# HASP_Electronics.net
KiCad netlist of a schematic drawn in EAGLE
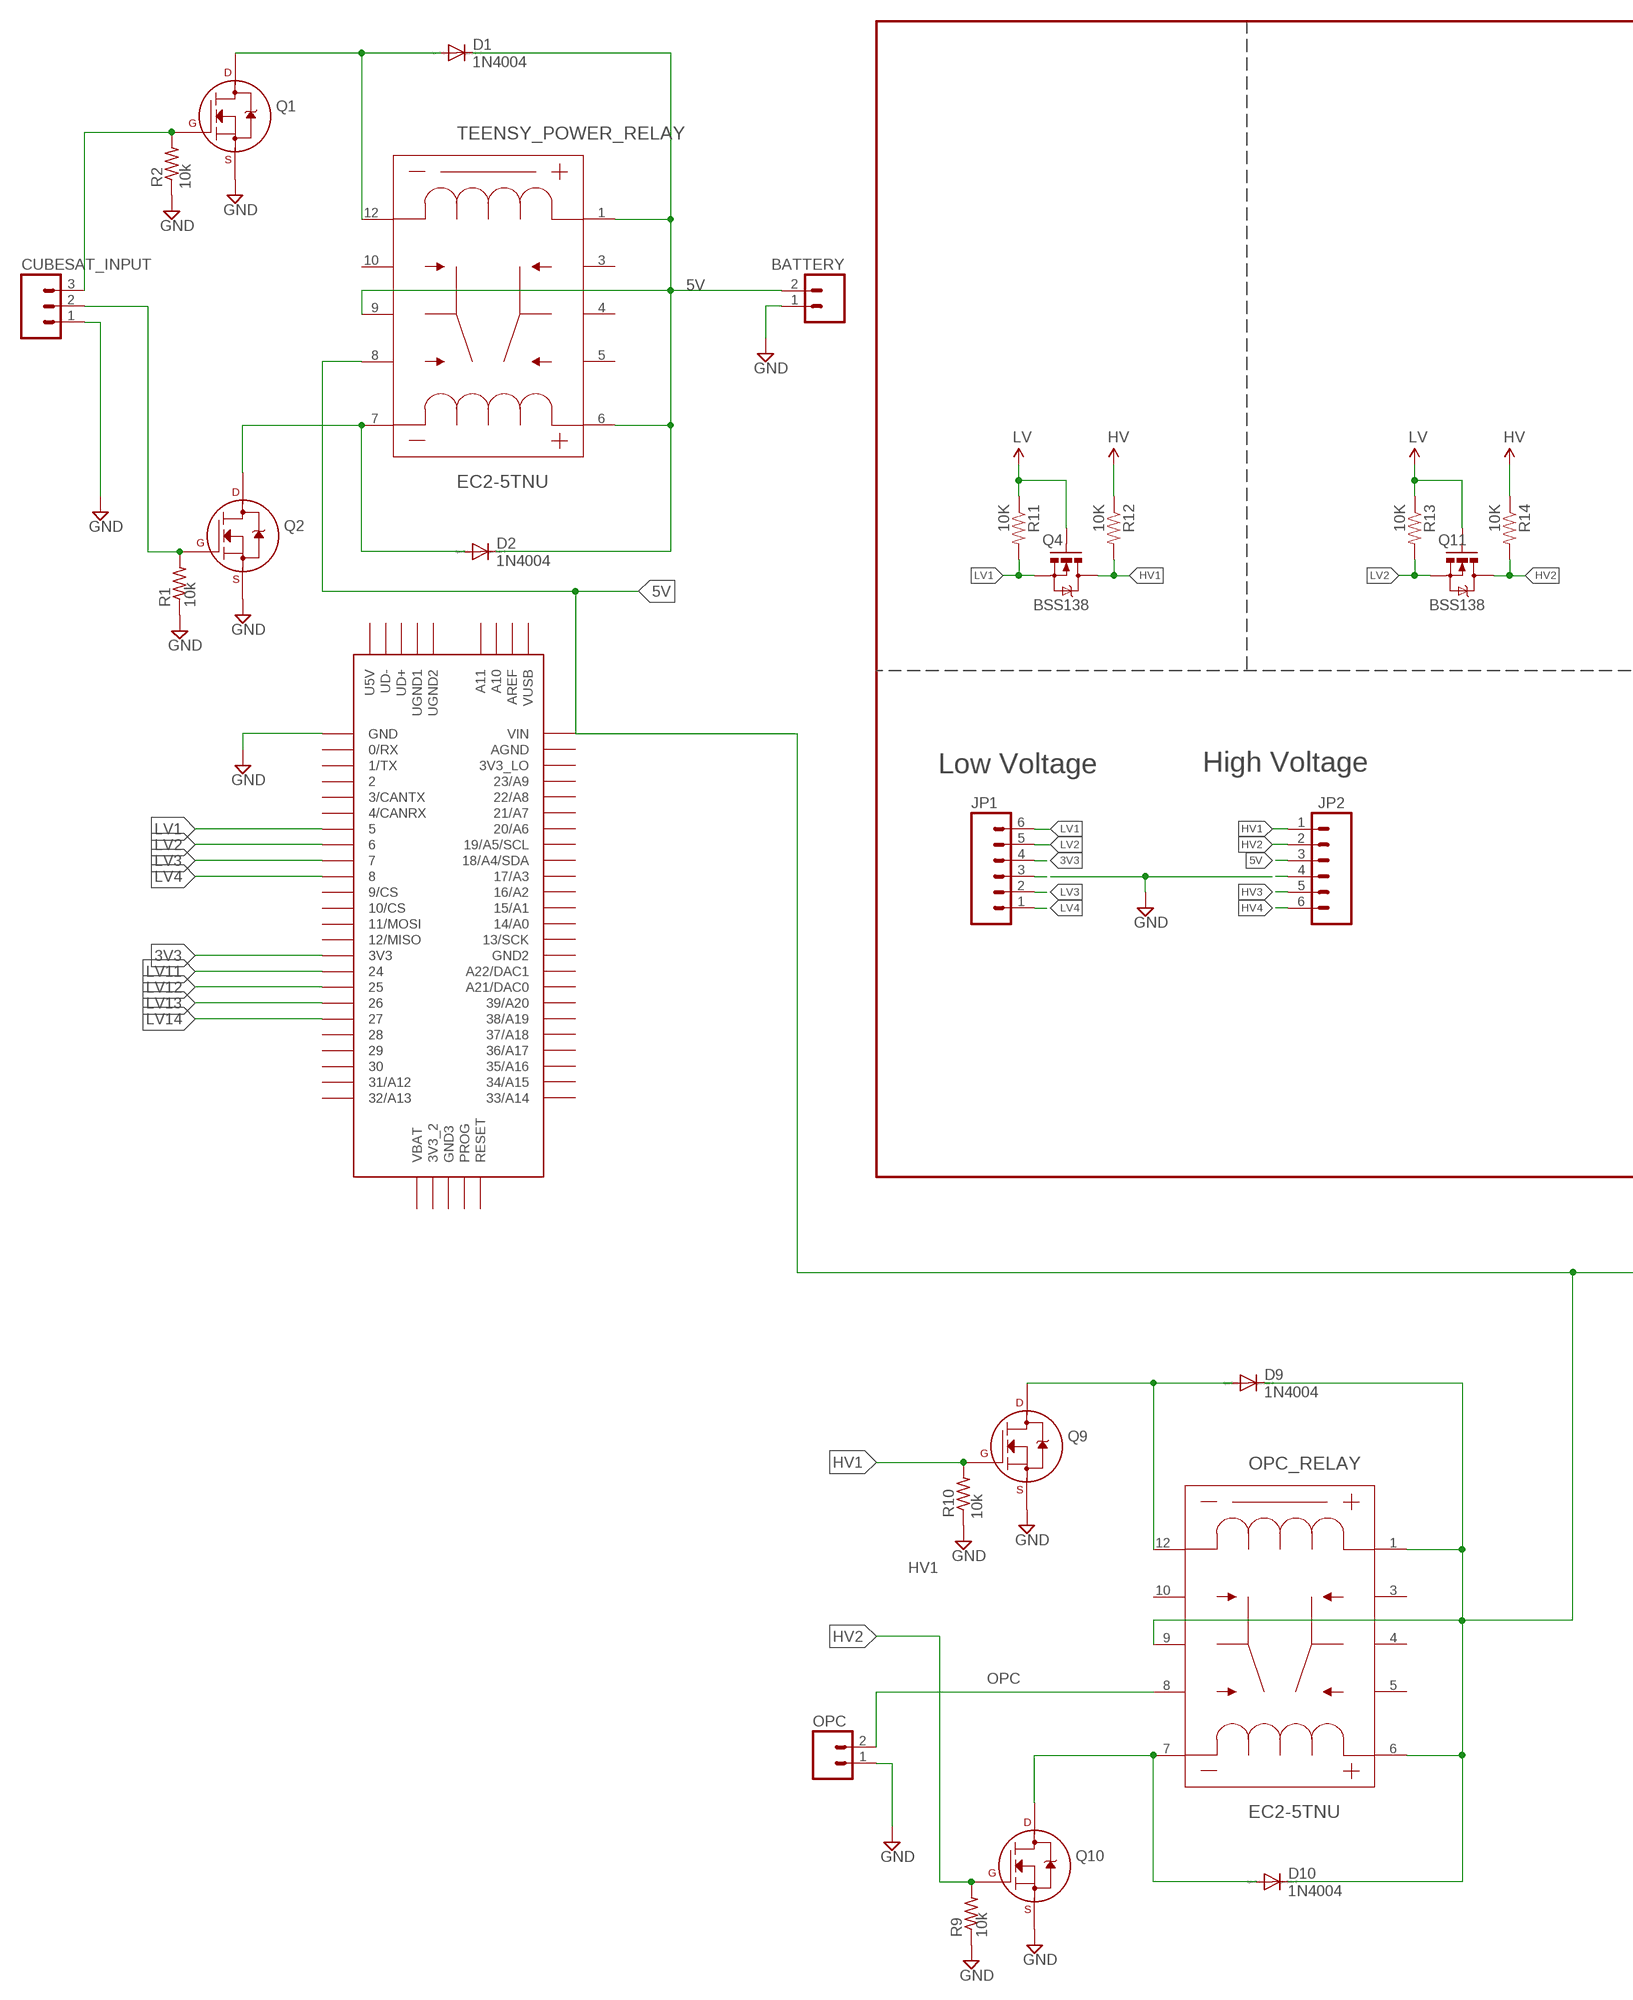
[diagram p0: schematic, sheet 1, part 1 of 2]
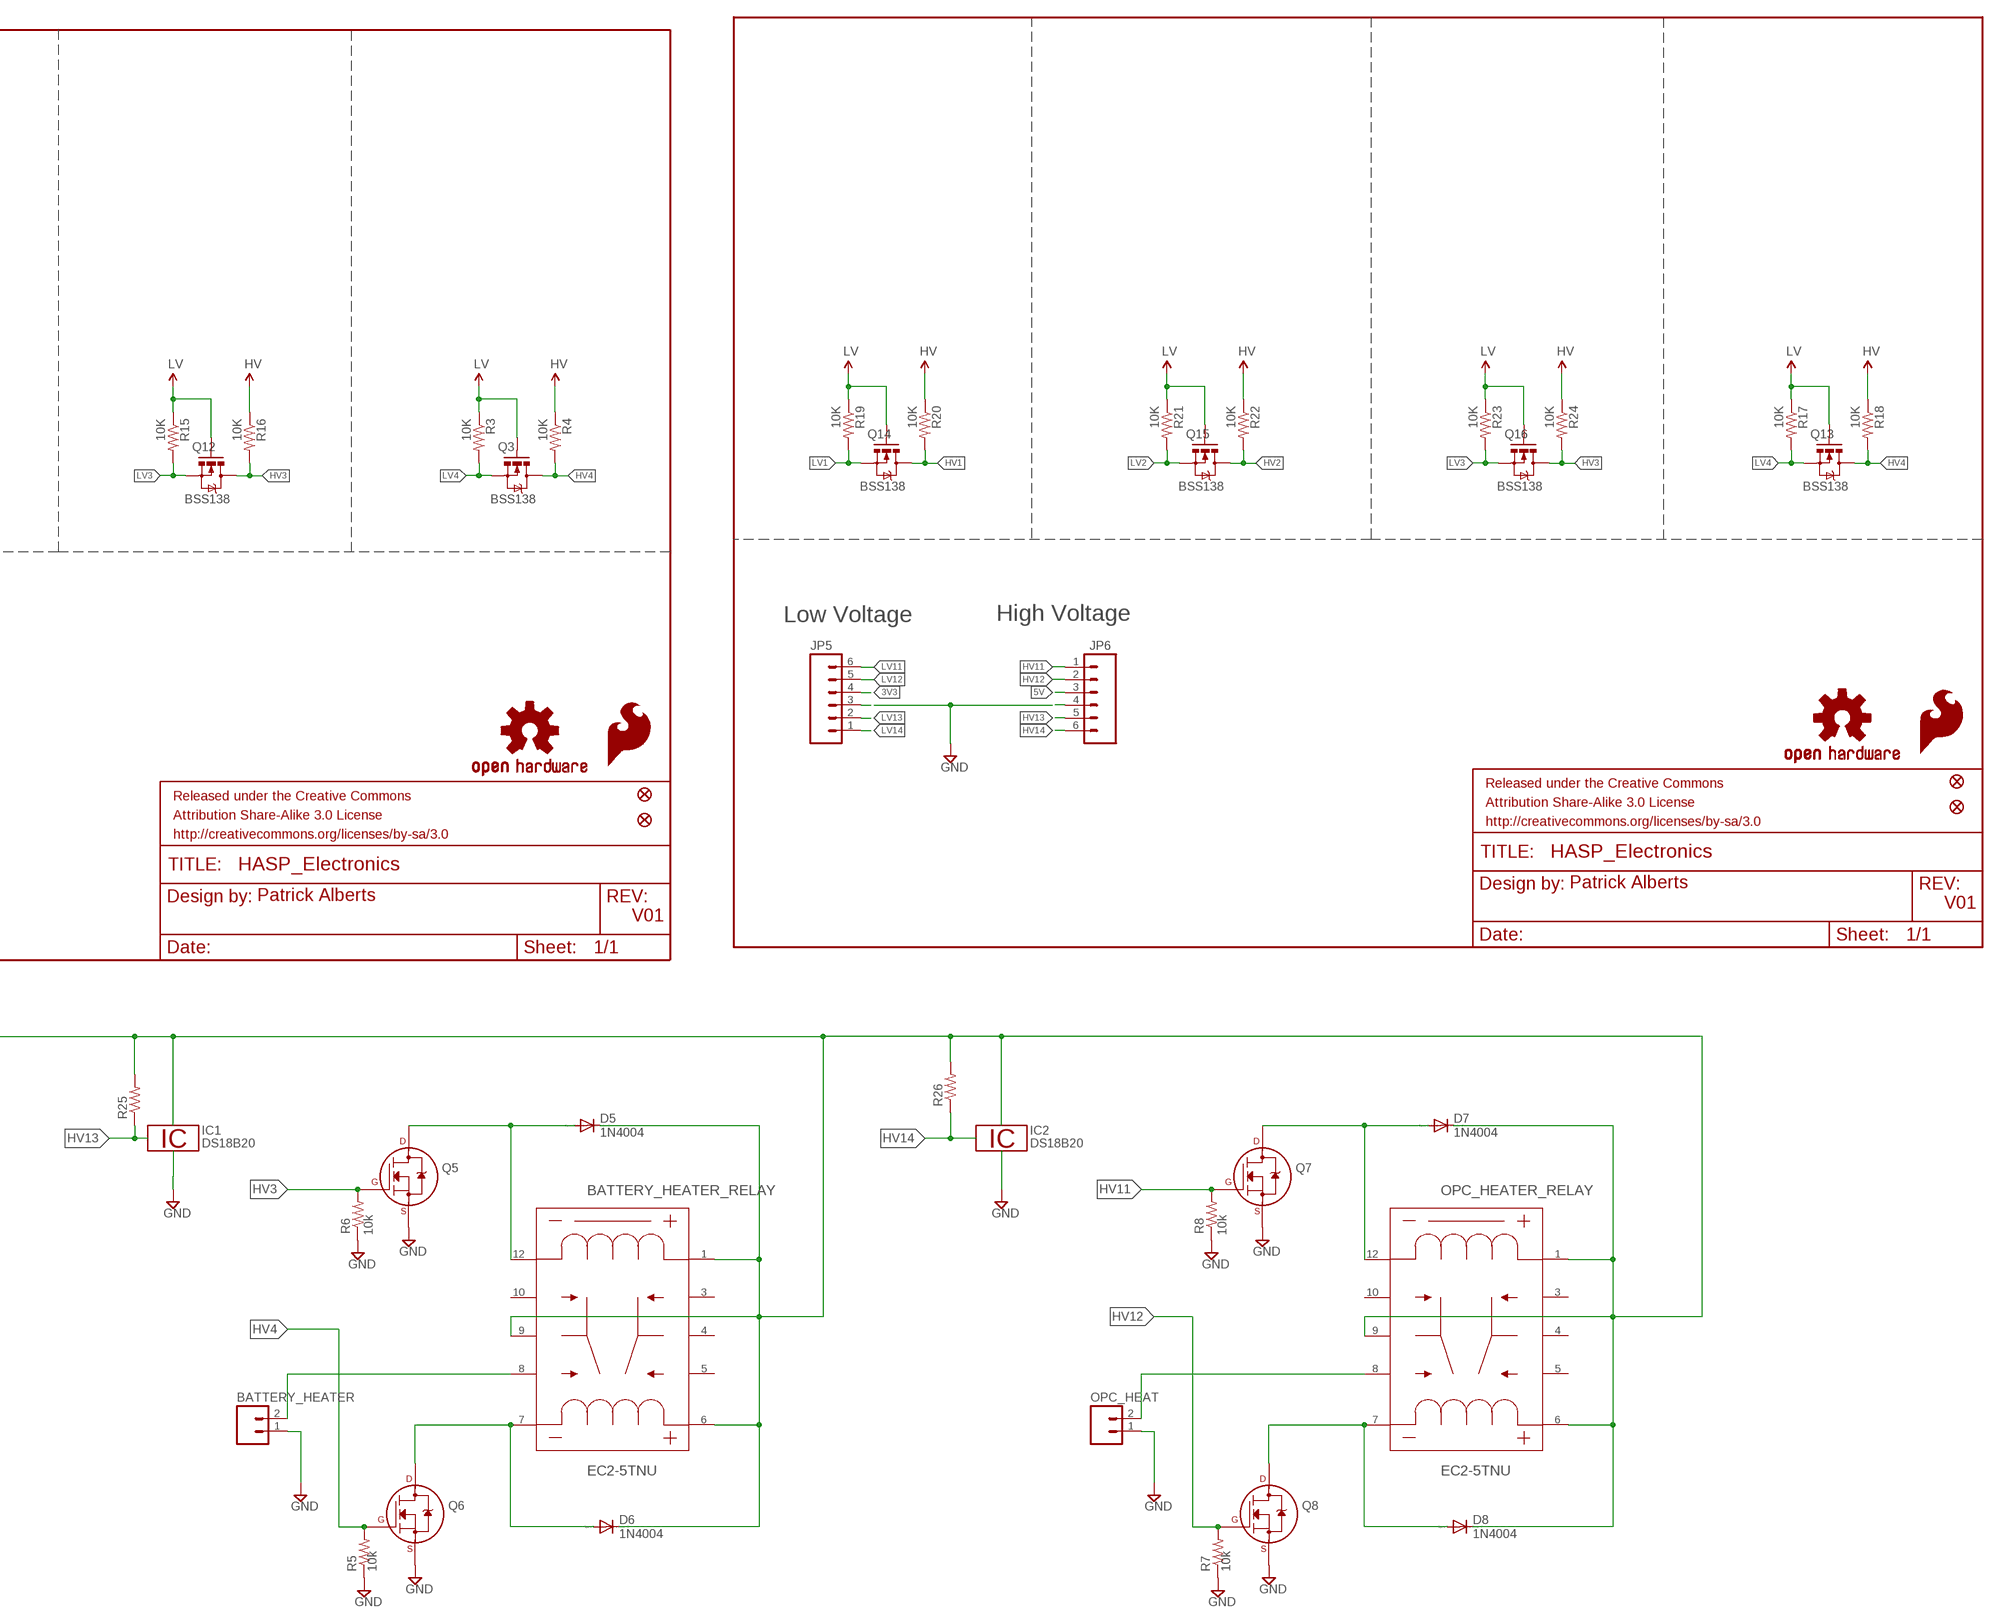
[diagram p1: schematic, sheet 1, part 2 of 2]

(export (version "E")
  (design (tool "Eeschema 10.0.6"))
  (components
    (comp (ref "BATTERY")
      (value "M02")
      (footprint "eagle-import:02P")
      (libsource (lib "eagle-import") (part "M02"))
    )
    (comp (ref "BATTERY_HEATER")
      (value "M02")
      (footprint "eagle-import:02P")
      (libsource (lib "eagle-import") (part "M02"))
    )
    (comp (ref "BATTERY_HEATER_RELAY")
      (value "EC2-5TNU")
      (footprint "eagle-import:EC2TNU")
      (fields (field (name "MANUFACTURER_PART_NUMBER") "EC25TNU"))
      (libsource (lib "eagle-import") (part "EC2-5TNU"))
    )
    (comp (ref "CUBESAT_INPUT")
      (value "M03")
      (footprint "eagle-import:03P")
      (libsource (lib "eagle-import") (part "M03"))
    )
    (comp (ref "D1")
      (value "1N4004")
      (footprint "eagle-import:DO41-10")
      (libsource (lib "eagle-import") (part "1N4004"))
    )
    (comp (ref "D2")
      (value "1N4004")
      (footprint "eagle-import:DO41-10")
      (libsource (lib "eagle-import") (part "1N4004"))
    )
    (comp (ref "D5")
      (value "1N4004")
      (footprint "eagle-import:DO41-10")
      (libsource (lib "eagle-import") (part "1N4004"))
    )
    (comp (ref "D6")
      (value "1N4004")
      (footprint "eagle-import:DO41-10")
      (libsource (lib "eagle-import") (part "1N4004"))
    )
    (comp (ref "D7")
      (value "1N4004")
      (footprint "eagle-import:DO41-10")
      (libsource (lib "eagle-import") (part "1N4004"))
    )
    (comp (ref "D8")
      (value "1N4004")
      (footprint "eagle-import:DO41-10")
      (libsource (lib "eagle-import") (part "1N4004"))
    )
    (comp (ref "D9")
      (value "1N4004")
      (footprint "eagle-import:DO41-10")
      (libsource (lib "eagle-import") (part "1N4004"))
    )
    (comp (ref "D10")
      (value "1N4004")
      (footprint "eagle-import:DO41-10")
      (libsource (lib "eagle-import") (part "1N4004"))
    )
    (comp (ref "IC1")
      (value "DS18B20")
      (footprint "eagle-import:TO92-")
      (libsource (lib "eagle-import") (part "DS18B20"))
    )
    (comp (ref "IC2")
      (value "DS18B20")
      (footprint "eagle-import:TO92-")
      (libsource (lib "eagle-import") (part "DS18B20"))
    )
    (comp (ref "JP1")
      (value "M06SIP")
      (footprint "eagle-import:1X06")
      (libsource (lib "eagle-import") (part "M06SIP"))
    )
    (comp (ref "JP2")
      (value "M06SIP")
      (footprint "eagle-import:1X06")
      (libsource (lib "eagle-import") (part "M06SIP"))
    )
    (comp (ref "JP3")
      (value "FIDUCIALUFIDUCIAL")
      (footprint "eagle-import:MICRO-FIDUCIAL")
      (libsource (lib "eagle-import") (part "FIDUCIALUFIDUCIAL"))
    )
    (comp (ref "JP4")
      (value "FIDUCIALUFIDUCIAL")
      (footprint "eagle-import:MICRO-FIDUCIAL")
      (libsource (lib "eagle-import") (part "FIDUCIALUFIDUCIAL"))
    )
    (comp (ref "JP5")
      (value "M06SIP")
      (footprint "eagle-import:1X06")
      (libsource (lib "eagle-import") (part "M06SIP"))
    )
    (comp (ref "JP6")
      (value "M06SIP")
      (footprint "eagle-import:1X06")
      (libsource (lib "eagle-import") (part "M06SIP"))
    )
    (comp (ref "JP7")
      (value "FIDUCIALUFIDUCIAL")
      (footprint "eagle-import:MICRO-FIDUCIAL")
      (libsource (lib "eagle-import") (part "FIDUCIALUFIDUCIAL"))
    )
    (comp (ref "JP8")
      (value "FIDUCIALUFIDUCIAL")
      (footprint "eagle-import:MICRO-FIDUCIAL")
      (libsource (lib "eagle-import") (part "FIDUCIALUFIDUCIAL"))
    )
    (comp (ref "LOGO1")
      (value "SFE_LOGO_FLAME.1_INCH")
      (footprint "eagle-import:SFE_LOGO_FLAME_.1")
      (libsource (lib "eagle-import") (part "SFE_LOGO_FLAME.1_INCH"))
    )
    (comp (ref "LOGO2")
      (value "OSHW-LOGOS")
      (footprint "eagle-import:OSHW-LOGO-S")
      (libsource (lib "eagle-import") (part "OSHW-LOGOS"))
    )
    (comp (ref "LOGO3")
      (value "SFE_LOGO_FLAME.1_INCH")
      (footprint "eagle-import:SFE_LOGO_FLAME_.1")
      (libsource (lib "eagle-import") (part "SFE_LOGO_FLAME.1_INCH"))
    )
    (comp (ref "LOGO4")
      (value "OSHW-LOGOS")
      (footprint "eagle-import:OSHW-LOGO-S")
      (libsource (lib "eagle-import") (part "OSHW-LOGOS"))
    )
    (comp (ref "OPC")
      (value "M02")
      (footprint "eagle-import:02P")
      (libsource (lib "eagle-import") (part "M02"))
    )
    (comp (ref "OPC_HEAT")
      (value "M02")
      (footprint "eagle-import:02P")
      (libsource (lib "eagle-import") (part "M02"))
    )
    (comp (ref "OPC_HEATER_RELAY")
      (value "EC2-5TNU")
      (footprint "eagle-import:EC2TNU")
      (fields (field (name "MANUFACTURER_PART_NUMBER") "EC25TNU"))
      (libsource (lib "eagle-import") (part "EC2-5TNU"))
    )
    (comp (ref "OPC_RELAY")
      (value "EC2-5TNU")
      (footprint "eagle-import:EC2TNU")
      (fields (field (name "MANUFACTURER_PART_NUMBER") "EC25TNU"))
      (libsource (lib "eagle-import") (part "EC2-5TNU"))
    )
    (comp (ref "Q1")
      (value "2N7000_TO92")
      (footprint "eagle-import:TO-92")
      (libsource (lib "eagle-import") (part "2N700_TO920"))
    )
    (comp (ref "Q2")
      (value "2N7000_TO92")
      (footprint "eagle-import:TO-92")
      (libsource (lib "eagle-import") (part "2N700_TO920"))
    )
    (comp (ref "Q3")
      (value "BSS138")
      (footprint "eagle-import:SOT23-3")
      (libsource (lib "eagle-import") (part "MOSFET-NCHANNELSMD"))
    )
    (comp (ref "Q4")
      (value "BSS138")
      (footprint "eagle-import:SOT23-3")
      (libsource (lib "eagle-import") (part "MOSFET-NCHANNELSMD"))
    )
    (comp (ref "Q5")
      (value "2N7000_TO92")
      (footprint "eagle-import:TO-92")
      (libsource (lib "eagle-import") (part "2N700_TO920"))
    )
    (comp (ref "Q6")
      (value "2N7000_TO92")
      (footprint "eagle-import:TO-92")
      (libsource (lib "eagle-import") (part "2N700_TO920"))
    )
    (comp (ref "Q7")
      (value "2N7000_TO92")
      (footprint "eagle-import:TO-92")
      (libsource (lib "eagle-import") (part "2N700_TO920"))
    )
    (comp (ref "Q8")
      (value "2N7000_TO92")
      (footprint "eagle-import:TO-92")
      (libsource (lib "eagle-import") (part "2N700_TO920"))
    )
    (comp (ref "Q9")
      (value "2N7000_TO92")
      (footprint "eagle-import:TO-92")
      (libsource (lib "eagle-import") (part "2N700_TO920"))
    )
    (comp (ref "Q10")
      (value "2N7000_TO92")
      (footprint "eagle-import:TO-92")
      (libsource (lib "eagle-import") (part "2N700_TO920"))
    )
    (comp (ref "Q11")
      (value "BSS138")
      (footprint "eagle-import:SOT23-3")
      (libsource (lib "eagle-import") (part "MOSFET-NCHANNELSMD"))
    )
    (comp (ref "Q12")
      (value "BSS138")
      (footprint "eagle-import:SOT23-3")
      (libsource (lib "eagle-import") (part "MOSFET-NCHANNELSMD"))
    )
    (comp (ref "Q13")
      (value "BSS138")
      (footprint "eagle-import:SOT23-3")
      (libsource (lib "eagle-import") (part "MOSFET-NCHANNELSMD"))
    )
    (comp (ref "Q14")
      (value "BSS138")
      (footprint "eagle-import:SOT23-3")
      (libsource (lib "eagle-import") (part "MOSFET-NCHANNELSMD"))
    )
    (comp (ref "Q15")
      (value "BSS138")
      (footprint "eagle-import:SOT23-3")
      (libsource (lib "eagle-import") (part "MOSFET-NCHANNELSMD"))
    )
    (comp (ref "Q16")
      (value "BSS138")
      (footprint "eagle-import:SOT23-3")
      (libsource (lib "eagle-import") (part "MOSFET-NCHANNELSMD"))
    )
    (comp (ref "R1")
      (value "R-US_0207/7")
      (footprint "eagle-import:0207_7")
      (libsource (lib "eagle-import") (part "R-US_0207/7"))
    )
    (comp (ref "R2")
      (value "R-US_0207/7")
      (footprint "eagle-import:0207_7")
      (libsource (lib "eagle-import") (part "R-US_0207/7"))
    )
    (comp (ref "R3")
      (value "10K")
      (footprint "eagle-import:0603-RES")
      (libsource (lib "eagle-import") (part "RESISTOR0603-RES"))
    )
    (comp (ref "R4")
      (value "10K")
      (footprint "eagle-import:0603-RES")
      (libsource (lib "eagle-import") (part "RESISTOR0603-RES"))
    )
    (comp (ref "R5")
      (value "R-US_0207/7")
      (footprint "eagle-import:0207_7")
      (libsource (lib "eagle-import") (part "R-US_0207/7"))
    )
    (comp (ref "R6")
      (value "R-US_0207/7")
      (footprint "eagle-import:0207_7")
      (libsource (lib "eagle-import") (part "R-US_0207/7"))
    )
    (comp (ref "R7")
      (value "R-US_0207/7")
      (footprint "eagle-import:0207_7")
      (libsource (lib "eagle-import") (part "R-US_0207/7"))
    )
    (comp (ref "R8")
      (value "R-US_0207/7")
      (footprint "eagle-import:0207_7")
      (libsource (lib "eagle-import") (part "R-US_0207/7"))
    )
    (comp (ref "R9")
      (value "R-US_0207/7")
      (footprint "eagle-import:0207_7")
      (libsource (lib "eagle-import") (part "R-US_0207/7"))
    )
    (comp (ref "R10")
      (value "R-US_0207/7")
      (footprint "eagle-import:0207_7")
      (libsource (lib "eagle-import") (part "R-US_0207/7"))
    )
    (comp (ref "R11")
      (value "10K")
      (footprint "eagle-import:0603-RES")
      (libsource (lib "eagle-import") (part "RESISTOR0603-RES"))
    )
    (comp (ref "R12")
      (value "10K")
      (footprint "eagle-import:0603-RES")
      (libsource (lib "eagle-import") (part "RESISTOR0603-RES"))
    )
    (comp (ref "R13")
      (value "10K")
      (footprint "eagle-import:0603-RES")
      (libsource (lib "eagle-import") (part "RESISTOR0603-RES"))
    )
    (comp (ref "R14")
      (value "10K")
      (footprint "eagle-import:0603-RES")
      (libsource (lib "eagle-import") (part "RESISTOR0603-RES"))
    )
    (comp (ref "R15")
      (value "10K")
      (footprint "eagle-import:0603-RES")
      (libsource (lib "eagle-import") (part "RESISTOR0603-RES"))
    )
    (comp (ref "R16")
      (value "10K")
      (footprint "eagle-import:0603-RES")
      (libsource (lib "eagle-import") (part "RESISTOR0603-RES"))
    )
    (comp (ref "R17")
      (value "10K")
      (footprint "eagle-import:0603-RES")
      (libsource (lib "eagle-import") (part "RESISTOR0603-RES"))
    )
    (comp (ref "R18")
      (value "10K")
      (footprint "eagle-import:0603-RES")
      (libsource (lib "eagle-import") (part "RESISTOR0603-RES"))
    )
    (comp (ref "R19")
      (value "10K")
      (footprint "eagle-import:0603-RES")
      (libsource (lib "eagle-import") (part "RESISTOR0603-RES"))
    )
    (comp (ref "R20")
      (value "10K")
      (footprint "eagle-import:0603-RES")
      (libsource (lib "eagle-import") (part "RESISTOR0603-RES"))
    )
    (comp (ref "R21")
      (value "10K")
      (footprint "eagle-import:0603-RES")
      (libsource (lib "eagle-import") (part "RESISTOR0603-RES"))
    )
    (comp (ref "R22")
      (value "10K")
      (footprint "eagle-import:0603-RES")
      (libsource (lib "eagle-import") (part "RESISTOR0603-RES"))
    )
    (comp (ref "R23")
      (value "10K")
      (footprint "eagle-import:0603-RES")
      (libsource (lib "eagle-import") (part "RESISTOR0603-RES"))
    )
    (comp (ref "R24")
      (value "10K")
      (footprint "eagle-import:0603-RES")
      (libsource (lib "eagle-import") (part "RESISTOR0603-RES"))
    )
    (comp (ref "R25")
      (value "R-US_0204/7")
      (footprint "eagle-import:0204_7")
      (libsource (lib "eagle-import") (part "resistor_348_R-US_0204/7"))
    )
    (comp (ref "R26")
      (value "R-US_0204/7")
      (footprint "eagle-import:0204_7")
      (libsource (lib "eagle-import") (part "resistor_348_R-US_0204/7"))
    )
    (comp (ref "TEENSY_POWER_RELAY")
      (value "EC2-5TNU")
      (footprint "eagle-import:EC2TNU")
      (fields (field (name "MANUFACTURER_PART_NUMBER") "EC25TNU"))
      (libsource (lib "eagle-import") (part "EC2-5TNU"))
    )
    (comp (ref "U$1")
      (value "TEENSY_3.5/3.6")
      (footprint "eagle-import:TEENSY_3.5_3.6")
      (libsource (lib "eagle-import") (part "TEENSY_3.5/3.6"))
    )
  )
  (nets
    (net (code "1") (name "/OPC") (class "Default")
      (node (ref "BATTERY_HEATER") (pin "2") (pinfunction "2_2") (pintype "passive"))
      (node (ref "BATTERY_HEATER_RELAY") (pin "8") (pinfunction "7_8") (pintype "passive"))
      (node (ref "OPC") (pin "2") (pinfunction "2_2") (pintype "passive"))
      (node (ref "OPC_RELAY") (pin "8") (pinfunction "7_8") (pintype "passive"))
    )
    (net (code "2") (name "3V3") (class "Default")
      (node (ref "JP1") (pin "4") (pinfunction "4_4") (pintype "passive"))
      (node (ref "JP5") (pin "4") (pinfunction "4_4") (pintype "passive"))
      (node (ref "U$1") (pin "3V3") (pinfunction "3V3_3V3") (pintype "bidirectional"))
    )
    (net (code "3") (name "5V") (class "Default")
      (node (ref "BATTERY") (pin "2") (pinfunction "2_2") (pintype "passive"))
      (node (ref "BATTERY_HEATER_RELAY") (pin "1") (pinfunction "1_1") (pintype "passive"))
      (node (ref "BATTERY_HEATER_RELAY") (pin "6") (pinfunction "5_6") (pintype "passive"))
      (node (ref "BATTERY_HEATER_RELAY") (pin "9") (pinfunction "8_9") (pintype "passive"))
      (node (ref "D1") (pin "C") (pinfunction "C_C") (pintype "passive"))
      (node (ref "D10") (pin "C") (pinfunction "C_C") (pintype "passive"))
      (node (ref "D2") (pin "C") (pinfunction "C_C") (pintype "passive"))
      (node (ref "D5") (pin "C") (pinfunction "C_C") (pintype "passive"))
      (node (ref "D6") (pin "C") (pinfunction "C_C") (pintype "passive"))
      (node (ref "D7") (pin "C") (pinfunction "C_C") (pintype "passive"))
      (node (ref "D8") (pin "C") (pinfunction "C_C") (pintype "passive"))
      (node (ref "D9") (pin "C") (pinfunction "C_C") (pintype "passive"))
      (node (ref "JP2") (pin "3") (pinfunction "3_3") (pintype "passive"))
      (node (ref "JP6") (pin "3") (pinfunction "3_3") (pintype "passive"))
      (node (ref "OPC_HEATER_RELAY") (pin "1") (pinfunction "1_1") (pintype "passive"))
      (node (ref "OPC_HEATER_RELAY") (pin "6") (pinfunction "5_6") (pintype "passive"))
      (node (ref "OPC_HEATER_RELAY") (pin "9") (pinfunction "8_9") (pintype "passive"))
      (node (ref "OPC_RELAY") (pin "1") (pinfunction "1_1") (pintype "passive"))
      (node (ref "OPC_RELAY") (pin "6") (pinfunction "5_6") (pintype "passive"))
      (node (ref "OPC_RELAY") (pin "9") (pinfunction "8_9") (pintype "passive"))
      (node (ref "R25") (pin "2") (pinfunction "2_2") (pintype "passive"))
      (node (ref "R26") (pin "2") (pinfunction "2_2") (pintype "passive"))
      (node (ref "TEENSY_POWER_RELAY") (pin "1") (pinfunction "1_1") (pintype "passive"))
      (node (ref "TEENSY_POWER_RELAY") (pin "6") (pinfunction "5_6") (pintype "passive"))
      (node (ref "TEENSY_POWER_RELAY") (pin "8") (pinfunction "7_8") (pintype "passive"))
      (node (ref "TEENSY_POWER_RELAY") (pin "9") (pinfunction "8_9") (pintype "passive"))
      (node (ref "U$1") (pin "VIN") (pinfunction "VIN_VIN") (pintype "bidirectional"))
    )
    (net (code "4") (name "GND") (class "Default")
      (node (ref "BATTERY") (pin "1") (pinfunction "1_1") (pintype "passive"))
      (node (ref "BATTERY_HEATER") (pin "1") (pinfunction "1_1") (pintype "passive"))
      (node (ref "CUBESAT_INPUT") (pin "1") (pinfunction "1_1") (pintype "passive"))
      (node (ref "JP1") (pin "3") (pinfunction "3_3") (pintype "passive"))
      (node (ref "JP2") (pin "4") (pinfunction "4_4") (pintype "passive"))
      (node (ref "JP5") (pin "3") (pinfunction "3_3") (pintype "passive"))
      (node (ref "JP6") (pin "4") (pinfunction "4_4") (pintype "passive"))
      (node (ref "OPC") (pin "1") (pinfunction "1_1") (pintype "passive"))
      (node (ref "OPC_HEAT") (pin "1") (pinfunction "1_1") (pintype "passive"))
      (node (ref "Q1") (pin "1") (pinfunction "S_1") (pintype "bidirectional"))
      (node (ref "Q10") (pin "1") (pinfunction "S_1") (pintype "bidirectional"))
      (node (ref "Q2") (pin "1") (pinfunction "S_1") (pintype "bidirectional"))
      (node (ref "Q5") (pin "1") (pinfunction "S_1") (pintype "bidirectional"))
      (node (ref "Q6") (pin "1") (pinfunction "S_1") (pintype "bidirectional"))
      (node (ref "Q7") (pin "1") (pinfunction "S_1") (pintype "bidirectional"))
      (node (ref "Q8") (pin "1") (pinfunction "S_1") (pintype "bidirectional"))
      (node (ref "Q9") (pin "1") (pinfunction "S_1") (pintype "bidirectional"))
      (node (ref "R1") (pin "1") (pinfunction "1_1") (pintype "passive"))
      (node (ref "R10") (pin "1") (pinfunction "1_1") (pintype "passive"))
      (node (ref "R2") (pin "1") (pinfunction "1_1") (pintype "passive"))
      (node (ref "R5") (pin "1") (pinfunction "1_1") (pintype "passive"))
      (node (ref "R6") (pin "1") (pinfunction "1_1") (pintype "passive"))
      (node (ref "R7") (pin "1") (pinfunction "1_1") (pintype "passive"))
      (node (ref "R8") (pin "1") (pinfunction "1_1") (pintype "passive"))
      (node (ref "R9") (pin "1") (pinfunction "1_1") (pintype "passive"))
      (node (ref "U$1") (pin "GND") (pinfunction "GND_GND") (pintype "bidirectional"))
    )
    (net (code "5") (name "HV") (class "Default")
      (node (ref "R12") (pin "1") (pinfunction "1_1") (pintype "passive"))
      (node (ref "R14") (pin "1") (pinfunction "1_1") (pintype "passive"))
      (node (ref "R16") (pin "1") (pinfunction "1_1") (pintype "passive"))
      (node (ref "R18") (pin "1") (pinfunction "1_1") (pintype "passive"))
      (node (ref "R20") (pin "1") (pinfunction "1_1") (pintype "passive"))
      (node (ref "R22") (pin "1") (pinfunction "1_1") (pintype "passive"))
      (node (ref "R24") (pin "1") (pinfunction "1_1") (pintype "passive"))
      (node (ref "R4") (pin "1") (pinfunction "1_1") (pintype "passive"))
    )
    (net (code "6") (name "HV1") (class "Default")
      (node (ref "JP2") (pin "1") (pinfunction "1_1") (pintype "passive"))
      (node (ref "Q14") (pin "3") (pinfunction "D_3") (pintype "passive"))
      (node (ref "Q4") (pin "3") (pinfunction "D_3") (pintype "passive"))
      (node (ref "Q9") (pin "2") (pinfunction "G_2") (pintype "tri_state"))
      (node (ref "R10") (pin "2") (pinfunction "2_2") (pintype "passive"))
      (node (ref "R12") (pin "2") (pinfunction "2_2") (pintype "passive"))
      (node (ref "R20") (pin "2") (pinfunction "2_2") (pintype "passive"))
    )
    (net (code "7") (name "HV2") (class "Default")
      (node (ref "JP2") (pin "2") (pinfunction "2_2") (pintype "passive"))
      (node (ref "Q10") (pin "2") (pinfunction "G_2") (pintype "tri_state"))
      (node (ref "Q11") (pin "3") (pinfunction "D_3") (pintype "passive"))
      (node (ref "Q15") (pin "3") (pinfunction "D_3") (pintype "passive"))
      (node (ref "R14") (pin "2") (pinfunction "2_2") (pintype "passive"))
      (node (ref "R22") (pin "2") (pinfunction "2_2") (pintype "passive"))
      (node (ref "R9") (pin "2") (pinfunction "2_2") (pintype "passive"))
    )
    (net (code "8") (name "HV3") (class "Default")
      (node (ref "JP2") (pin "5") (pinfunction "5_5") (pintype "passive"))
      (node (ref "Q12") (pin "3") (pinfunction "D_3") (pintype "passive"))
      (node (ref "Q16") (pin "3") (pinfunction "D_3") (pintype "passive"))
      (node (ref "Q5") (pin "2") (pinfunction "G_2") (pintype "tri_state"))
      (node (ref "R16") (pin "2") (pinfunction "2_2") (pintype "passive"))
      (node (ref "R24") (pin "2") (pinfunction "2_2") (pintype "passive"))
      (node (ref "R6") (pin "2") (pinfunction "2_2") (pintype "passive"))
    )
    (net (code "9") (name "HV4") (class "Default")
      (node (ref "JP2") (pin "6") (pinfunction "6_6") (pintype "passive"))
      (node (ref "Q13") (pin "3") (pinfunction "D_3") (pintype "passive"))
      (node (ref "Q3") (pin "3") (pinfunction "D_3") (pintype "passive"))
      (node (ref "Q6") (pin "2") (pinfunction "G_2") (pintype "tri_state"))
      (node (ref "R18") (pin "2") (pinfunction "2_2") (pintype "passive"))
      (node (ref "R4") (pin "2") (pinfunction "2_2") (pintype "passive"))
      (node (ref "R5") (pin "2") (pinfunction "2_2") (pintype "passive"))
    )
    (net (code "10") (name "HV11") (class "Default")
      (node (ref "JP6") (pin "1") (pinfunction "1_1") (pintype "passive"))
      (node (ref "Q7") (pin "2") (pinfunction "G_2") (pintype "tri_state"))
      (node (ref "R8") (pin "2") (pinfunction "2_2") (pintype "passive"))
    )
    (net (code "11") (name "HV12") (class "Default")
      (node (ref "JP6") (pin "2") (pinfunction "2_2") (pintype "passive"))
      (node (ref "Q8") (pin "2") (pinfunction "G_2") (pintype "tri_state"))
      (node (ref "R7") (pin "2") (pinfunction "2_2") (pintype "passive"))
    )
    (net (code "12") (name "HV13") (class "Default")
      (node (ref "JP6") (pin "5") (pinfunction "5_5") (pintype "passive"))
      (node (ref "R25") (pin "1") (pinfunction "1_1") (pintype "passive"))
    )
    (net (code "13") (name "HV14") (class "Default")
      (node (ref "JP6") (pin "6") (pinfunction "6_6") (pintype "passive"))
      (node (ref "R26") (pin "1") (pinfunction "1_1") (pintype "passive"))
    )
    (net (code "14") (name "LV") (class "Default")
      (node (ref "Q11") (pin "1") (pinfunction "G_1") (pintype "passive"))
      (node (ref "Q12") (pin "1") (pinfunction "G_1") (pintype "passive"))
      (node (ref "Q13") (pin "1") (pinfunction "G_1") (pintype "passive"))
      (node (ref "Q14") (pin "1") (pinfunction "G_1") (pintype "passive"))
      (node (ref "Q15") (pin "1") (pinfunction "G_1") (pintype "passive"))
      (node (ref "Q16") (pin "1") (pinfunction "G_1") (pintype "passive"))
      (node (ref "Q3") (pin "1") (pinfunction "G_1") (pintype "passive"))
      (node (ref "Q4") (pin "1") (pinfunction "G_1") (pintype "passive"))
      (node (ref "R11") (pin "1") (pinfunction "1_1") (pintype "passive"))
      (node (ref "R13") (pin "1") (pinfunction "1_1") (pintype "passive"))
      (node (ref "R15") (pin "1") (pinfunction "1_1") (pintype "passive"))
      (node (ref "R17") (pin "1") (pinfunction "1_1") (pintype "passive"))
      (node (ref "R19") (pin "1") (pinfunction "1_1") (pintype "passive"))
      (node (ref "R21") (pin "1") (pinfunction "1_1") (pintype "passive"))
      (node (ref "R23") (pin "1") (pinfunction "1_1") (pintype "passive"))
      (node (ref "R3") (pin "1") (pinfunction "1_1") (pintype "passive"))
    )
    (net (code "15") (name "LV1") (class "Default")
      (node (ref "JP1") (pin "6") (pinfunction "6_6") (pintype "passive"))
      (node (ref "Q14") (pin "2") (pinfunction "S_2") (pintype "passive"))
      (node (ref "Q4") (pin "2") (pinfunction "S_2") (pintype "passive"))
      (node (ref "R11") (pin "2") (pinfunction "2_2") (pintype "passive"))
      (node (ref "R19") (pin "2") (pinfunction "2_2") (pintype "passive"))
      (node (ref "U$1") (pin "5") (pinfunction "5_5") (pintype "bidirectional"))
    )
    (net (code "16") (name "LV2") (class "Default")
      (node (ref "JP1") (pin "5") (pinfunction "5_5") (pintype "passive"))
      (node (ref "Q11") (pin "2") (pinfunction "S_2") (pintype "passive"))
      (node (ref "Q15") (pin "2") (pinfunction "S_2") (pintype "passive"))
      (node (ref "R13") (pin "2") (pinfunction "2_2") (pintype "passive"))
      (node (ref "R21") (pin "2") (pinfunction "2_2") (pintype "passive"))
      (node (ref "U$1") (pin "6") (pinfunction "6_6") (pintype "bidirectional"))
    )
    (net (code "17") (name "LV3") (class "Default")
      (node (ref "JP1") (pin "2") (pinfunction "2_2") (pintype "passive"))
      (node (ref "Q12") (pin "2") (pinfunction "S_2") (pintype "passive"))
      (node (ref "Q16") (pin "2") (pinfunction "S_2") (pintype "passive"))
      (node (ref "R15") (pin "2") (pinfunction "2_2") (pintype "passive"))
      (node (ref "R23") (pin "2") (pinfunction "2_2") (pintype "passive"))
      (node (ref "U$1") (pin "7") (pinfunction "7_7") (pintype "bidirectional"))
    )
    (net (code "18") (name "LV4") (class "Default")
      (node (ref "JP1") (pin "1") (pinfunction "1_1") (pintype "passive"))
      (node (ref "Q13") (pin "2") (pinfunction "S_2") (pintype "passive"))
      (node (ref "Q3") (pin "2") (pinfunction "S_2") (pintype "passive"))
      (node (ref "R17") (pin "2") (pinfunction "2_2") (pintype "passive"))
      (node (ref "R3") (pin "2") (pinfunction "2_2") (pintype "passive"))
      (node (ref "U$1") (pin "8") (pinfunction "8_8") (pintype "bidirectional"))
    )
    (net (code "19") (name "LV11") (class "Default")
      (node (ref "JP5") (pin "6") (pinfunction "6_6") (pintype "passive"))
      (node (ref "U$1") (pin "24") (pinfunction "24_24") (pintype "bidirectional"))
    )
    (net (code "20") (name "LV12") (class "Default")
      (node (ref "JP5") (pin "5") (pinfunction "5_5") (pintype "passive"))
      (node (ref "U$1") (pin "25") (pinfunction "25_25") (pintype "bidirectional"))
    )
    (net (code "21") (name "LV13") (class "Default")
      (node (ref "JP5") (pin "2") (pinfunction "2_2") (pintype "passive"))
      (node (ref "U$1") (pin "26") (pinfunction "26_26") (pintype "bidirectional"))
    )
    (net (code "22") (name "LV14") (class "Default")
      (node (ref "JP5") (pin "1") (pinfunction "1_1") (pintype "passive"))
      (node (ref "U$1") (pin "27") (pinfunction "27_27") (pintype "bidirectional"))
    )
    (net (code "23") (name "Net-(BATTERY_HEATER_RELAY-6)") (class "Default")
      (node (ref "BATTERY_HEATER_RELAY") (pin "7") (pinfunction "6_7") (pintype "passive"))
      (node (ref "D6") (pin "A") (pinfunction "A_A") (pintype "passive"))
      (node (ref "Q6") (pin "3") (pinfunction "D_3") (pintype "bidirectional"))
    )
    (net (code "24") (name "Net-(BATTERY_HEATER_RELAY-10)") (class "Default")
      (node (ref "BATTERY_HEATER_RELAY") (pin "12") (pinfunction "10_12") (pintype "passive"))
      (node (ref "D5") (pin "A") (pinfunction "A_A") (pintype "passive"))
      (node (ref "Q5") (pin "3") (pinfunction "D_3") (pintype "bidirectional"))
    )
    (net (code "25") (name "Net-(OPC_HEATER_RELAY-6)") (class "Default")
      (node (ref "D8") (pin "A") (pinfunction "A_A") (pintype "passive"))
      (node (ref "OPC_HEATER_RELAY") (pin "7") (pinfunction "6_7") (pintype "passive"))
      (node (ref "Q8") (pin "3") (pinfunction "D_3") (pintype "bidirectional"))
    )
    (net (code "26") (name "Net-(OPC_HEATER_RELAY-7)") (class "Default")
      (node (ref "OPC_HEAT") (pin "2") (pinfunction "2_2") (pintype "passive"))
      (node (ref "OPC_HEATER_RELAY") (pin "8") (pinfunction "7_8") (pintype "passive"))
    )
    (net (code "27") (name "Net-(OPC_HEATER_RELAY-10)") (class "Default")
      (node (ref "D7") (pin "A") (pinfunction "A_A") (pintype "passive"))
      (node (ref "OPC_HEATER_RELAY") (pin "12") (pinfunction "10_12") (pintype "passive"))
      (node (ref "Q7") (pin "3") (pinfunction "D_3") (pintype "bidirectional"))
    )
    (net (code "28") (name "Net-(OPC_RELAY-6)") (class "Default")
      (node (ref "D10") (pin "A") (pinfunction "A_A") (pintype "passive"))
      (node (ref "OPC_RELAY") (pin "7") (pinfunction "6_7") (pintype "passive"))
      (node (ref "Q10") (pin "3") (pinfunction "D_3") (pintype "bidirectional"))
    )
    (net (code "29") (name "Net-(OPC_RELAY-10)") (class "Default")
      (node (ref "D9") (pin "A") (pinfunction "A_A") (pintype "passive"))
      (node (ref "OPC_RELAY") (pin "12") (pinfunction "10_12") (pintype "passive"))
      (node (ref "Q9") (pin "3") (pinfunction "D_3") (pintype "bidirectional"))
    )
    (net (code "30") (name "Net-(Q1-D)") (class "Default")
      (node (ref "D1") (pin "A") (pinfunction "A_A") (pintype "passive"))
      (node (ref "Q1") (pin "3") (pinfunction "D_3") (pintype "bidirectional"))
      (node (ref "TEENSY_POWER_RELAY") (pin "12") (pinfunction "10_12") (pintype "passive"))
    )
    (net (code "31") (name "Net-(Q1-G)") (class "Default")
      (node (ref "CUBESAT_INPUT") (pin "3") (pinfunction "3_3") (pintype "passive"))
      (node (ref "Q1") (pin "2") (pinfunction "G_2") (pintype "tri_state"))
      (node (ref "R2") (pin "2") (pinfunction "2_2") (pintype "passive"))
    )
    (net (code "32") (name "Net-(Q2-D)") (class "Default")
      (node (ref "D2") (pin "A") (pinfunction "A_A") (pintype "passive"))
      (node (ref "Q2") (pin "3") (pinfunction "D_3") (pintype "bidirectional"))
      (node (ref "TEENSY_POWER_RELAY") (pin "7") (pinfunction "6_7") (pintype "passive"))
    )
    (net (code "33") (name "Net-(Q2-G)") (class "Default")
      (node (ref "CUBESAT_INPUT") (pin "2") (pinfunction "2_2") (pintype "passive"))
      (node (ref "Q2") (pin "2") (pinfunction "G_2") (pintype "tri_state"))
      (node (ref "R1") (pin "2") (pinfunction "2_2") (pintype "passive"))
    )
    (net (code "34") (name "unconnected-(BATTERY_HEATER_RELAY-2-Pad3)") (class "Default")
      (node (ref "BATTERY_HEATER_RELAY") (pin "3") (pinfunction "2_3") (pintype "passive"))
    )
    (net (code "35") (name "unconnected-(BATTERY_HEATER_RELAY-3-Pad4)") (class "Default")
      (node (ref "BATTERY_HEATER_RELAY") (pin "4") (pinfunction "3_4") (pintype "passive"))
    )
    (net (code "36") (name "unconnected-(BATTERY_HEATER_RELAY-4-Pad5)") (class "Default")
      (node (ref "BATTERY_HEATER_RELAY") (pin "5") (pinfunction "4_5") (pintype "passive"))
    )
    (net (code "37") (name "unconnected-(BATTERY_HEATER_RELAY-9-Pad10)") (class "Default")
      (node (ref "BATTERY_HEATER_RELAY") (pin "10") (pinfunction "9_10") (pintype "passive"))
    )
    (net (code "38") (name "unconnected-(OPC_HEATER_RELAY-2-Pad3)") (class "Default")
      (node (ref "OPC_HEATER_RELAY") (pin "3") (pinfunction "2_3") (pintype "passive"))
    )
    (net (code "39") (name "unconnected-(OPC_HEATER_RELAY-3-Pad4)") (class "Default")
      (node (ref "OPC_HEATER_RELAY") (pin "4") (pinfunction "3_4") (pintype "passive"))
    )
    (net (code "40") (name "unconnected-(OPC_HEATER_RELAY-4-Pad5)") (class "Default")
      (node (ref "OPC_HEATER_RELAY") (pin "5") (pinfunction "4_5") (pintype "passive"))
    )
    (net (code "41") (name "unconnected-(OPC_HEATER_RELAY-9-Pad10)") (class "Default")
      (node (ref "OPC_HEATER_RELAY") (pin "10") (pinfunction "9_10") (pintype "passive"))
    )
    (net (code "42") (name "unconnected-(OPC_RELAY-2-Pad3)") (class "Default")
      (node (ref "OPC_RELAY") (pin "3") (pinfunction "2_3") (pintype "passive"))
    )
    (net (code "43") (name "unconnected-(OPC_RELAY-3-Pad4)") (class "Default")
      (node (ref "OPC_RELAY") (pin "4") (pinfunction "3_4") (pintype "passive"))
    )
    (net (code "44") (name "unconnected-(OPC_RELAY-4-Pad5)") (class "Default")
      (node (ref "OPC_RELAY") (pin "5") (pinfunction "4_5") (pintype "passive"))
    )
    (net (code "45") (name "unconnected-(OPC_RELAY-9-Pad10)") (class "Default")
      (node (ref "OPC_RELAY") (pin "10") (pinfunction "9_10") (pintype "passive"))
    )
    (net (code "46") (name "unconnected-(TEENSY_POWER_RELAY-2-Pad3)") (class "Default")
      (node (ref "TEENSY_POWER_RELAY") (pin "3") (pinfunction "2_3") (pintype "passive"))
    )
    (net (code "47") (name "unconnected-(TEENSY_POWER_RELAY-3-Pad4)") (class "Default")
      (node (ref "TEENSY_POWER_RELAY") (pin "4") (pinfunction "3_4") (pintype "passive"))
    )
    (net (code "48") (name "unconnected-(TEENSY_POWER_RELAY-4-Pad5)") (class "Default")
      (node (ref "TEENSY_POWER_RELAY") (pin "5") (pinfunction "4_5") (pintype "passive"))
    )
    (net (code "49") (name "unconnected-(TEENSY_POWER_RELAY-9-Pad10)") (class "Default")
      (node (ref "TEENSY_POWER_RELAY") (pin "10") (pinfunction "9_10") (pintype "passive"))
    )
    (net (code "50") (name "unconnected-(U$1-A21{slash}DAC0-Pad21{slash}DAC0)") (class "Default")
      (node (ref "U$1") (pin "21/DAC0") (pinfunction "A21/DAC0_21/DAC0") (pintype "bidirectional"))
    )
    (net (code "51") (name "unconnected-(U$1-Pad0{slash}RX)") (class "Default")
      (node (ref "U$1") (pin "0/RX") (pinfunction "0/RX_0/RX") (pintype "bidirectional"))
    )
    (net (code "52") (name "unconnected-(U$1-Pad1{slash}TX)") (class "Default")
      (node (ref "U$1") (pin "1/TX") (pinfunction "1/TX_1/TX") (pintype "bidirectional"))
    )
    (net (code "53") (name "unconnected-(U$1-Pad2)") (class "Default")
      (node (ref "U$1") (pin "2") (pinfunction "2_2") (pintype "bidirectional"))
    )
    (net (code "54") (name "unconnected-(U$1-Pad3V3_2)") (class "Default")
      (node (ref "U$1") (pin "3V3_2") (pinfunction "3V3_2_3V3_2") (pintype "bidirectional"))
    )
    (net (code "55") (name "unconnected-(U$1-Pad3V3_LO)") (class "Default")
      (node (ref "U$1") (pin "3V3_LO") (pinfunction "3V3_LO_3V3_LO") (pintype "bidirectional"))
    )
    (net (code "56") (name "unconnected-(U$1-Pad3{slash}CANTX)") (class "Default")
      (node (ref "U$1") (pin "3/CANTX") (pinfunction "3/CANTX_3/CANTX") (pintype "bidirectional"))
    )
    (net (code "57") (name "unconnected-(U$1-Pad4{slash}CANRX)") (class "Default")
      (node (ref "U$1") (pin "4/CANRX") (pinfunction "4/CANRX_4/CANRX") (pintype "bidirectional"))
    )
    (net (code "58") (name "unconnected-(U$1-Pad9{slash}CS)") (class "Default")
      (node (ref "U$1") (pin "9/CS") (pinfunction "9/CS_9/CS") (pintype "bidirectional"))
    )
    (net (code "59") (name "unconnected-(U$1-Pad10{slash}CS)") (class "Default")
      (node (ref "U$1") (pin "10/CS") (pinfunction "10/CS_10/CS") (pintype "bidirectional"))
    )
    (net (code "60") (name "unconnected-(U$1-Pad11{slash}MOSI)") (class "Default")
      (node (ref "U$1") (pin "11/MOSI") (pinfunction "11/MOSI_11/MOSI") (pintype "bidirectional"))
    )
    (net (code "61") (name "unconnected-(U$1-Pad12{slash}MISO)") (class "Default")
      (node (ref "U$1") (pin "12/MISO") (pinfunction "12/MISO_12/MISO") (pintype "bidirectional"))
    )
    (net (code "62") (name "unconnected-(U$1-Pad13{slash}SCK)") (class "Default")
      (node (ref "U$1") (pin "13/SCK") (pinfunction "13/SCK_13/SCK") (pintype "bidirectional"))
    )
    (net (code "63") (name "unconnected-(U$1-Pad14{slash}A0)") (class "Default")
      (node (ref "U$1") (pin "14/A0") (pinfunction "14/A0_14/A0") (pintype "bidirectional"))
    )
    (net (code "64") (name "unconnected-(U$1-Pad15{slash}A1)") (class "Default")
      (node (ref "U$1") (pin "15/A1") (pinfunction "15/A1_15/A1") (pintype "bidirectional"))
    )
    (net (code "65") (name "unconnected-(U$1-Pad16{slash}A2)") (class "Default")
      (node (ref "U$1") (pin "16/A2") (pinfunction "16/A2_16/A2") (pintype "bidirectional"))
    )
    (net (code "66") (name "unconnected-(U$1-Pad17{slash}A3)") (class "Default")
      (node (ref "U$1") (pin "17/A3") (pinfunction "17/A3_17/A3") (pintype "bidirectional"))
    )
    (net (code "67") (name "unconnected-(U$1-Pad18{slash}A4{slash}SDA)") (class "Default")
      (node (ref "U$1") (pin "18/A4/SDA") (pinfunction "18/A4/SDA_18/A4/SDA") (pintype "bidirectional"))
    )
    (net (code "68") (name "unconnected-(U$1-Pad19{slash}A5{slash}SCL)") (class "Default")
      (node (ref "U$1") (pin "19/A5/SCL") (pinfunction "19/A5/SCL_19/A5/SCL") (pintype "bidirectional"))
    )
    (net (code "69") (name "unconnected-(U$1-Pad20{slash}A6)") (class "Default")
      (node (ref "U$1") (pin "20/A6") (pinfunction "20/A6_20/A6") (pintype "bidirectional"))
    )
    (net (code "70") (name "unconnected-(U$1-Pad21{slash}A7)") (class "Default")
      (node (ref "U$1") (pin "21/A7") (pinfunction "21/A7_21/A7") (pintype "bidirectional"))
    )
    (net (code "71") (name "unconnected-(U$1-Pad22{slash}A8)") (class "Default")
      (node (ref "U$1") (pin "22/A8") (pinfunction "22/A8_22/A8") (pintype "bidirectional"))
    )
    (net (code "72") (name "unconnected-(U$1-Pad23{slash}A9)") (class "Default")
      (node (ref "U$1") (pin "23/A9") (pinfunction "23/A9_23/A9") (pintype "bidirectional"))
    )
    (net (code "73") (name "unconnected-(U$1-Pad28)") (class "Default")
      (node (ref "U$1") (pin "28") (pinfunction "28_28") (pintype "bidirectional"))
    )
    (net (code "74") (name "unconnected-(U$1-Pad29)") (class "Default")
      (node (ref "U$1") (pin "29") (pinfunction "29_29") (pintype "bidirectional"))
    )
    (net (code "75") (name "unconnected-(U$1-Pad30)") (class "Default")
      (node (ref "U$1") (pin "30") (pinfunction "30_30") (pintype "bidirectional"))
    )
    (net (code "76") (name "unconnected-(U$1-Pad31{slash}A12)") (class "Default")
      (node (ref "U$1") (pin "31/A12") (pinfunction "31/A12_31/A12") (pintype "bidirectional"))
    )
    (net (code "77") (name "unconnected-(U$1-Pad32{slash}A13)") (class "Default")
      (node (ref "U$1") (pin "32/A13") (pinfunction "32/A13_32/A13") (pintype "bidirectional"))
    )
    (net (code "78") (name "unconnected-(U$1-Pad33{slash}A14)") (class "Default")
      (node (ref "U$1") (pin "33/A14") (pinfunction "33/A14_33/A14") (pintype "bidirectional"))
    )
    (net (code "79") (name "unconnected-(U$1-Pad34{slash}A15)") (class "Default")
      (node (ref "U$1") (pin "34/A15") (pinfunction "34/A15_34/A15") (pintype "bidirectional"))
    )
    (net (code "80") (name "unconnected-(U$1-Pad35{slash}A16)") (class "Default")
      (node (ref "U$1") (pin "35/A16") (pinfunction "35/A16_35/A16") (pintype "bidirectional"))
    )
    (net (code "81") (name "unconnected-(U$1-Pad36{slash}A17)") (class "Default")
      (node (ref "U$1") (pin "36/A17") (pinfunction "36/A17_36/A17") (pintype "bidirectional"))
    )
    (net (code "82") (name "unconnected-(U$1-Pad37{slash}A18)") (class "Default")
      (node (ref "U$1") (pin "37/A18") (pinfunction "37/A18_37/A18") (pintype "bidirectional"))
    )
    (net (code "83") (name "unconnected-(U$1-Pad38{slash}A19)") (class "Default")
      (node (ref "U$1") (pin "38/A19") (pinfunction "38/A19_38/A19") (pintype "bidirectional"))
    )
    (net (code "84") (name "unconnected-(U$1-Pad39{slash}A20)") (class "Default")
      (node (ref "U$1") (pin "39/A20") (pinfunction "39/A20_39/A20") (pintype "bidirectional"))
    )
    (net (code "85") (name "unconnected-(U$1-PadA10)") (class "Default")
      (node (ref "U$1") (pin "A10") (pinfunction "A10_A10") (pintype "bidirectional"))
    )
    (net (code "86") (name "unconnected-(U$1-PadA11)") (class "Default")
      (node (ref "U$1") (pin "A11") (pinfunction "A11_A11") (pintype "bidirectional"))
    )
    (net (code "87") (name "unconnected-(U$1-PadA22{slash}DAC1)") (class "Default")
      (node (ref "U$1") (pin "A22/DAC1") (pinfunction "A22/DAC1_A22/DAC1") (pintype "bidirectional"))
    )
    (net (code "88") (name "unconnected-(U$1-PadAGND)") (class "Default")
      (node (ref "U$1") (pin "AGND") (pinfunction "AGND_AGND") (pintype "bidirectional"))
    )
    (net (code "89") (name "unconnected-(U$1-PadAREF)") (class "Default")
      (node (ref "U$1") (pin "AREF") (pinfunction "AREF_AREF") (pintype "bidirectional"))
    )
    (net (code "90") (name "unconnected-(U$1-PadGND2)") (class "Default")
      (node (ref "U$1") (pin "GND2") (pinfunction "GND2_GND2") (pintype "bidirectional"))
    )
    (net (code "91") (name "unconnected-(U$1-PadGND3)") (class "Default")
      (node (ref "U$1") (pin "GND3") (pinfunction "GND3_GND3") (pintype "bidirectional"))
    )
    (net (code "92") (name "unconnected-(U$1-PadPROG)") (class "Default")
      (node (ref "U$1") (pin "PROG") (pinfunction "PROG_PROG") (pintype "bidirectional"))
    )
    (net (code "93") (name "unconnected-(U$1-PadRESET)") (class "Default")
      (node (ref "U$1") (pin "RESET") (pinfunction "RESET_RESET") (pintype "bidirectional"))
    )
    (net (code "94") (name "unconnected-(U$1-PadU5V)") (class "Default")
      (node (ref "U$1") (pin "U5V") (pinfunction "U5V_U5V") (pintype "bidirectional"))
    )
    (net (code "95") (name "unconnected-(U$1-PadUD+)") (class "Default")
      (node (ref "U$1") (pin "UD+") (pinfunction "UD+_UD+") (pintype "bidirectional"))
    )
    (net (code "96") (name "unconnected-(U$1-PadUD-)") (class "Default")
      (node (ref "U$1") (pin "UD-") (pinfunction "UD-_UD-") (pintype "bidirectional"))
    )
    (net (code "97") (name "unconnected-(U$1-PadUGND1)") (class "Default")
      (node (ref "U$1") (pin "UGND1") (pinfunction "UGND1_UGND1") (pintype "bidirectional"))
    )
    (net (code "98") (name "unconnected-(U$1-PadUGND2)") (class "Default")
      (node (ref "U$1") (pin "UGND2") (pinfunction "UGND2_UGND2") (pintype "bidirectional"))
    )
    (net (code "99") (name "unconnected-(U$1-PadVBAT)") (class "Default")
      (node (ref "U$1") (pin "VBAT") (pinfunction "VBAT_VBAT") (pintype "bidirectional"))
    )
    (net (code "100") (name "unconnected-(U$1-PadVUSB)") (class "Default")
      (node (ref "U$1") (pin "VUSB") (pinfunction "VUSB_VUSB") (pintype "bidirectional"))
    )
  )
)
